# powerup_button.net
KiCad netlist of a schematic drawn in Altium Designer
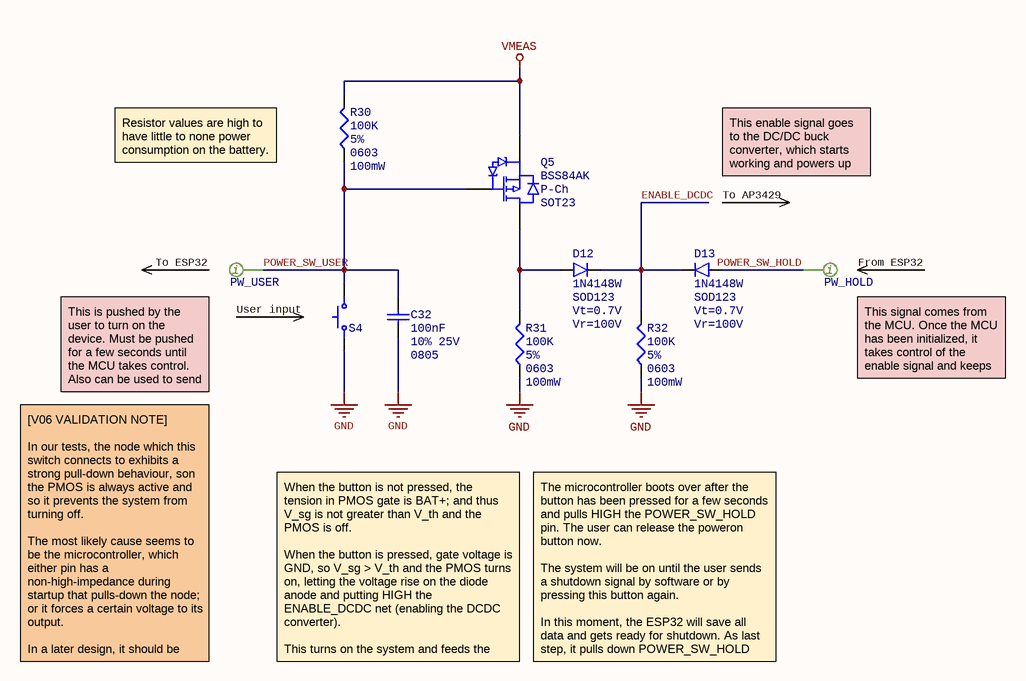
[diagram p0: powerup_button.SchDoc]

(export (version "E")
  (design (tool "Eeschema 10.0.6"))
  (components
    (comp (ref "C32")
      (value "100nF")
      (footprint "CAP 0805_2012")
      (description "Ceramic cap size 0805")
      (fields
        (field (name "TOLERANCE") "10% 25V")
        (field (name "PACKAGEDESCRIPTION") "0805")
        (field (name "Comment") "Cap_cer_0805")
      )
      (libsource (lib "tik_handheld_schlib") (part "Cap_cer_0805_100nF_10%"))
    )
    (comp (ref "D12")
      (value "Diode 1N4148W")
      (footprint "SOD123F 1N4148W")
      (description "SURFACE MOUNT FAST SWITCHING DIODE")
      (fields
        (field (name "PART") "1N4148W")
        (field (name "PACKAGEDESCRIPTION") "SOD123")
        (field (name "FORWARDVOLTAGE") "Vt=0.7V")
        (field (name "REVERSEVOLTAGE") "Vr=100V")
      )
      (libsource (lib "tik_handheld_schlib") (part "Diode 1N4148W"))
    )
    (comp (ref "D13")
      (value "Diode 1N4148W")
      (footprint "SOD123F 1N4148W")
      (description "SURFACE MOUNT FAST SWITCHING DIODE")
      (fields
        (field (name "PART") "1N4148W")
        (field (name "PACKAGEDESCRIPTION") "SOD123")
        (field (name "FORWARDVOLTAGE") "Vt=0.7V")
        (field (name "REVERSEVOLTAGE") "Vr=100V")
      )
      (libsource (lib "tik_handheld_schlib") (part "Diode 1N4148W"))
    )
    (comp (ref "PW_HOLD")
      (value "Test Point Pad dual sided")
      (footprint "TEST POINT PAD")
      (description "Test point - PCB Pad dual sided")
      (libsource (lib "tik_handheld_schlib") (part "Test Point Pad dual sided"))
    )
    (comp (ref "PW_USER")
      (value "Test Point Pad dual sided")
      (footprint "TEST POINT PAD")
      (description "Test point - PCB Pad dual sided")
      (libsource (lib "tik_handheld_schlib") (part "Test Point Pad dual sided"))
    )
    (comp (ref "Q5")
      (value "PMOS BSS84AK")
      (footprint "SOT-23-3 TO-236AB 2N7002")
      (fields
        (field (name "PART") "BSS84AK")
        (field (name "TYPE") "P-Ch")
        (field (name "PACKAGEDESCRIPTION") "SOT23")
      )
      (libsource (lib "tik_handheld_schlib") (part "PMOS BSS84AK"))
    )
    (comp (ref "R30")
      (value "100K")
      (footprint "RES 0603_1608")
      (description "Res size 0603 SMD mounting, low power")
      (fields
        (field (name "TOLERANCE") "5%")
        (field (name "PACKAGEDESCRIPTION") "0603")
        (field (name "POWERDISIPATED") "100mW")
        (field (name "Comment") "Res_0603_100K_5%_100mW")
      )
      (libsource (lib "tik_handheld_schlib") (part "Res_0603_100K_5%_100mW"))
    )
    (comp (ref "R31")
      (value "100K")
      (footprint "RES 0603_1608")
      (description "Res size 0603 SMD mounting, low power")
      (fields
        (field (name "TOLERANCE") "5%")
        (field (name "PACKAGEDESCRIPTION") "0603")
        (field (name "POWERDISIPATED") "100mW")
        (field (name "Comment") "Res_0603_100K_5%_100mW")
      )
      (libsource (lib "tik_handheld_schlib") (part "Res_0603_100K_5%_100mW"))
    )
    (comp (ref "R32")
      (value "100K")
      (footprint "RES 0603_1608")
      (description "Res size 0603 SMD mounting, low power")
      (fields
        (field (name "TOLERANCE") "5%")
        (field (name "PACKAGEDESCRIPTION") "0603")
        (field (name "POWERDISIPATED") "100mW")
        (field (name "Comment") "Res_0603_100K_5%_100mW")
      )
      (libsource (lib "tik_handheld_schlib") (part "Res_0603_100K_5%_100mW"))
    )
    (comp (ref "S4")
      (value "Button")
      (footprint "button generic")
      (description "Generic 2 pin button")
      (libsource (lib "tik_handheld_schlib") (part "Button"))
    )
  )
  (nets
    (net (code "1") (name "/ENABLE_DCDC") (class "Default")
      (node (ref "D12") (pin "2") (pinfunction "2_2") (pintype "passive"))
      (node (ref "D13") (pin "2") (pinfunction "2_2") (pintype "passive"))
      (node (ref "R32") (pin "2") (pinfunction "2_2") (pintype "passive"))
    )
    (net (code "2") (name "/POWER_SW_HOLD") (class "Default")
      (node (ref "D13") (pin "1") (pinfunction "1_1") (pintype "passive"))
      (node (ref "PW_HOLD") (pin "1") (pinfunction "1_1") (pintype "passive"))
    )
    (net (code "3") (name "/POWER_SW_USER") (class "Default")
      (node (ref "C32") (pin "2") (pinfunction "2_2") (pintype "passive"))
      (node (ref "PW_USER") (pin "1") (pinfunction "1_1") (pintype "passive"))
      (node (ref "Q5") (pin "1") (pinfunction "G_1") (pintype "passive"))
      (node (ref "R30") (pin "1") (pinfunction "1_1") (pintype "passive"))
      (node (ref "S4") (pin "2") (pinfunction "2_2") (pintype "passive"))
    )
    (net (code "4") (name "GND") (class "Default")
      (node (ref "C32") (pin "1") (pinfunction "1_1") (pintype "passive"))
      (node (ref "R31") (pin "1") (pinfunction "1_1") (pintype "passive"))
      (node (ref "R32") (pin "1") (pinfunction "1_1") (pintype "passive"))
      (node (ref "S4") (pin "1") (pinfunction "1_1") (pintype "passive"))
    )
    (net (code "5") (name "Net-(Q5-D)") (class "Default")
      (node (ref "D12") (pin "1") (pinfunction "1_1") (pintype "passive"))
      (node (ref "Q5") (pin "3") (pinfunction "D_3") (pintype "passive"))
      (node (ref "R31") (pin "2") (pinfunction "2_2") (pintype "passive"))
    )
    (net (code "6") (name "VMEAS") (class "Default")
      (node (ref "Q5") (pin "2") (pinfunction "S_2") (pintype "passive"))
      (node (ref "R30") (pin "2") (pinfunction "2_2") (pintype "passive"))
    )
  )
)
